# CAN_node_analog.net
KiCad netlist of a schematic drawn in EAGLE
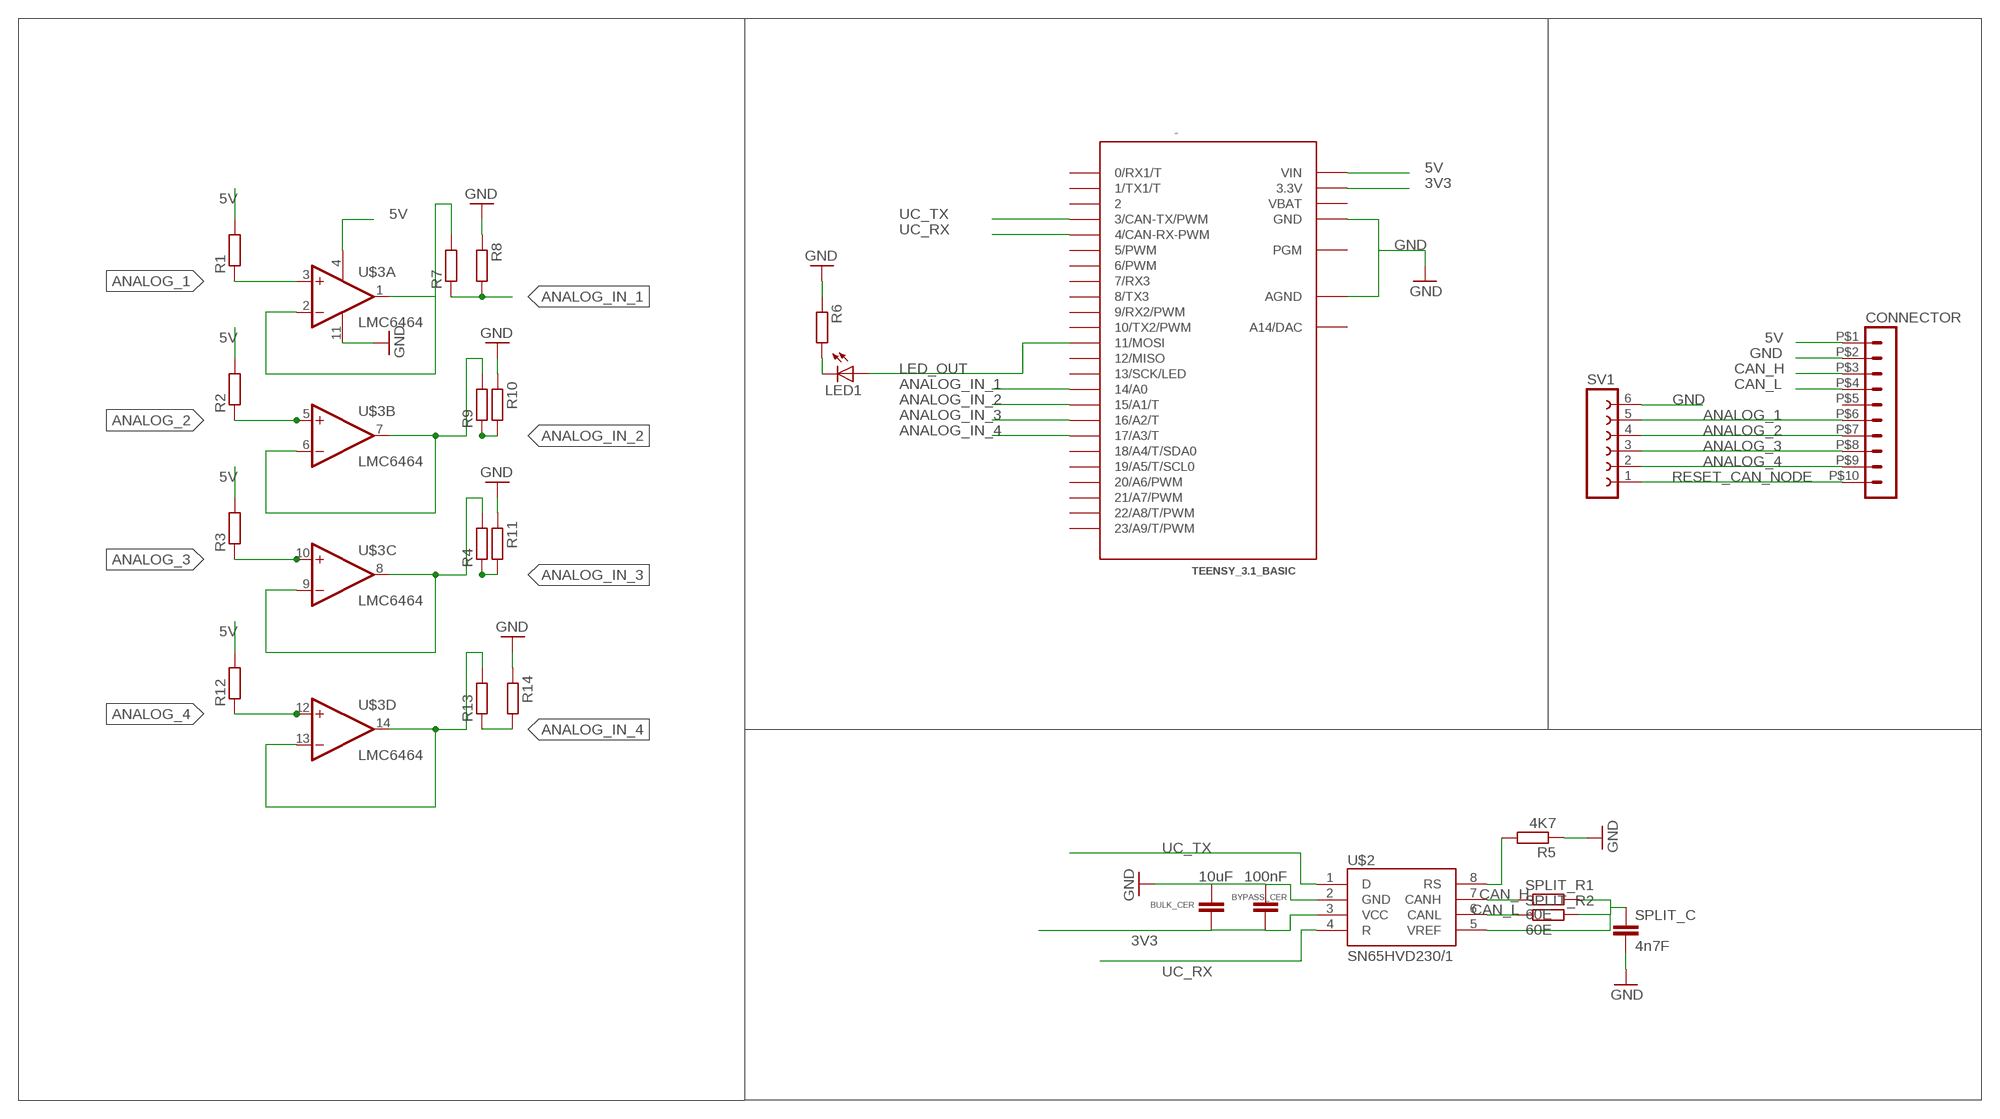
[diagram p0: schematic, sheet 1]

(export (version "E")
  (design (tool "Eeschema 10.0.6"))
  (components
    (comp (ref "BULK_CER")
      (value "10uF")
      (footprint "eagle-import:C0805")
      (libsource (lib "eagle-import") (part "C-EUC0805"))
    )
    (comp (ref "BYPASS_CER")
      (value "100nF")
      (footprint "eagle-import:C0805")
      (libsource (lib "eagle-import") (part "C-EUC0805"))
    )
    (comp (ref "CONNECTOR")
      (value "HEADER_POS10_43045-1012")
      (footprint "eagle-import:43045-1012")
      (libsource (lib "eagle-import") (part "HEADER_POS10_?43045-1012"))
    )
    (comp (ref "LED1")
      (value "LED1206")
      (footprint "eagle-import:LED-1206")
      (libsource (lib "eagle-import") (part "LED1206"))
    )
    (comp (ref "R1")
      (value "R-EU_R0805")
      (footprint "eagle-import:R0805")
      (libsource (lib "eagle-import") (part "R-EU_R0805"))
    )
    (comp (ref "R2")
      (value "R-EU_R0805")
      (footprint "eagle-import:R0805")
      (libsource (lib "eagle-import") (part "R-EU_R0805"))
    )
    (comp (ref "R3")
      (value "R-EU_R0805")
      (footprint "eagle-import:R0805")
      (libsource (lib "eagle-import") (part "R-EU_R0805"))
    )
    (comp (ref "R4")
      (value "R-EU_R0805")
      (footprint "eagle-import:R0805")
      (libsource (lib "eagle-import") (part "R-EU_R0805"))
    )
    (comp (ref "R5")
      (value "4K7")
      (footprint "eagle-import:R0805")
      (libsource (lib "eagle-import") (part "LV_R-EU_R0805"))
    )
    (comp (ref "R6")
      (value "R-EU_R0805")
      (footprint "eagle-import:R0805")
      (libsource (lib "eagle-import") (part "R-EU_R0805"))
    )
    (comp (ref "R7")
      (value "R-EU_R0805")
      (footprint "eagle-import:R0805")
      (libsource (lib "eagle-import") (part "R-EU_R0805"))
    )
    (comp (ref "R8")
      (value "R-EU_R0805")
      (footprint "eagle-import:R0805")
      (libsource (lib "eagle-import") (part "R-EU_R0805"))
    )
    (comp (ref "R9")
      (value "R-EU_R0805")
      (footprint "eagle-import:R0805")
      (libsource (lib "eagle-import") (part "R-EU_R0805"))
    )
    (comp (ref "R10")
      (value "R-EU_R0805")
      (footprint "eagle-import:R0805")
      (libsource (lib "eagle-import") (part "R-EU_R0805"))
    )
    (comp (ref "R11")
      (value "R-EU_R0805")
      (footprint "eagle-import:R0805")
      (libsource (lib "eagle-import") (part "R-EU_R0805"))
    )
    (comp (ref "R12")
      (value "R-EU_R0805")
      (footprint "eagle-import:R0805")
      (libsource (lib "eagle-import") (part "R-EU_R0805"))
    )
    (comp (ref "R13")
      (value "R-EU_R0805")
      (footprint "eagle-import:R0805")
      (libsource (lib "eagle-import") (part "R-EU_R0805"))
    )
    (comp (ref "R14")
      (value "R-EU_R0805")
      (footprint "eagle-import:R0805")
      (libsource (lib "eagle-import") (part "R-EU_R0805"))
    )
    (comp (ref "SPLIT_C")
      (value "4n7F")
      (footprint "eagle-import:C0805")
      (libsource (lib "eagle-import") (part "C-EUC0805"))
    )
    (comp (ref "SPLIT_R1")
      (value "60E")
      (footprint "eagle-import:R0805")
      (libsource (lib "eagle-import") (part "LV_R-EU_R0805"))
    )
    (comp (ref "SPLIT_R2")
      (value "60E")
      (footprint "eagle-import:R0805")
      (libsource (lib "eagle-import") (part "LV_R-EU_R0805"))
    )
    (comp (ref "SV1")
      (value "FE06-1")
      (footprint "eagle-import:FE06")
      (libsource (lib "eagle-import") (part "FE06-1"))
    )
    (comp (ref "U$1")
      (value "TEENSY_3.1_BASIC")
      (footprint "eagle-import:TEENSY_3.1_BASIC")
      (libsource (lib "eagle-import") (part "TEENSY_3.1_BASIC"))
    )
    (comp (ref "U$2")
      (value "SN65HVD230/1")
      (footprint "eagle-import:SO8")
      (libsource (lib "eagle-import") (part "SN65HVD230/1"))
    )
    (comp (ref "U$3")
      (value "LMC6464")
      (footprint "eagle-import:SO14_LONGPADS")
      (libsource (lib "eagle-import") (part "LMC6464"))
    )
  )
  (nets
    (net (code "1") (name "/3V3") (class "Default")
      (node (ref "BULK_CER") (pin "1") (pinfunction "1_1") (pintype "passive"))
      (node (ref "BYPASS_CER") (pin "1") (pinfunction "1_1") (pintype "passive"))
      (node (ref "U$1") (pin "3.3V") (pinfunction "3.3V_3.3V") (pintype "power_in"))
      (node (ref "U$1") (pin "3.3V1") (pinfunction "3.3V_3.3V1") (pintype "power_in"))
      (node (ref "U$2") (pin "3") (pinfunction "VCC_3") (pintype "power_in"))
    )
    (net (code "2") (name "/5V") (class "Default")
      (node (ref "CONNECTOR") (pin "P$1") (pinfunction "1_P$1") (pintype "passive"))
      (node (ref "R1") (pin "2") (pinfunction "2_2") (pintype "passive"))
      (node (ref "R12") (pin "2") (pinfunction "2_2") (pintype "passive"))
      (node (ref "R2") (pin "2") (pinfunction "2_2") (pintype "passive"))
      (node (ref "R3") (pin "2") (pinfunction "2_2") (pintype "passive"))
      (node (ref "U$1") (pin "VIN") (pinfunction "VIN_VIN") (pintype "power_in"))
      (node (ref "U$3") (pin "4") (pinfunction "V+_4") (pintype "power_in"))
    )
    (net (code "3") (name "/CAN_H") (class "Default")
      (node (ref "CONNECTOR") (pin "P$3") (pinfunction "3_P$3") (pintype "passive"))
      (node (ref "SPLIT_R1") (pin "1") (pinfunction "1_1") (pintype "passive"))
      (node (ref "U$2") (pin "7") (pinfunction "CANH_7") (pintype "bidirectional"))
    )
    (net (code "4") (name "/CAN_L") (class "Default")
      (node (ref "CONNECTOR") (pin "P$4") (pinfunction "4_P$4") (pintype "passive"))
      (node (ref "SPLIT_R2") (pin "1") (pinfunction "1_1") (pintype "passive"))
      (node (ref "U$2") (pin "6") (pinfunction "CANL_6") (pintype "bidirectional"))
    )
    (net (code "5") (name "/LED_OUT") (class "Default")
      (node (ref "LED1") (pin "A") (pinfunction "A_A") (pintype "passive"))
      (node (ref "U$1") (pin "11") (pinfunction "11/MOSI_11") (pintype "bidirectional"))
    )
    (net (code "6") (name "/RESET_CAN_NODE") (class "Default")
      (node (ref "CONNECTOR") (pin "P$10") (pinfunction "10_P$10") (pintype "passive"))
      (node (ref "SV1") (pin "1") (pinfunction "1_1") (pintype "passive"))
    )
    (net (code "7") (name "/UC_RX") (class "Default")
      (node (ref "U$1") (pin "4") (pinfunction "4/CAN-RX-PWM_4") (pintype "bidirectional"))
      (node (ref "U$2") (pin "4") (pinfunction "R_4") (pintype "bidirectional"))
    )
    (net (code "8") (name "/UC_TX") (class "Default")
      (node (ref "U$1") (pin "3") (pinfunction "3/CAN-TX/PWM_3") (pintype "bidirectional"))
      (node (ref "U$2") (pin "1") (pinfunction "D_1") (pintype "bidirectional"))
    )
    (net (code "9") (name "/VBAT") (class "Default")
      (node (ref "U$1") (pin "VBAT") (pinfunction "VBAT_VBAT") (pintype "power_in"))
    )
    (net (code "10") (name "ANALOG_1") (class "Default")
      (node (ref "CONNECTOR") (pin "P$6") (pinfunction "6_P$6") (pintype "passive"))
      (node (ref "R1") (pin "1") (pinfunction "1_1") (pintype "passive"))
      (node (ref "SV1") (pin "5") (pinfunction "5_5") (pintype "passive"))
      (node (ref "U$3") (pin "3") (pinfunction "+IN_3") (pintype "input"))
    )
    (net (code "11") (name "ANALOG_2") (class "Default")
      (node (ref "CONNECTOR") (pin "P$7") (pinfunction "7_P$7") (pintype "passive"))
      (node (ref "R2") (pin "1") (pinfunction "1_1") (pintype "passive"))
      (node (ref "SV1") (pin "4") (pinfunction "4_4") (pintype "passive"))
      (node (ref "U$3") (pin "5") (pinfunction "+IN_5") (pintype "input"))
    )
    (net (code "12") (name "ANALOG_3") (class "Default")
      (node (ref "CONNECTOR") (pin "P$8") (pinfunction "8_P$8") (pintype "passive"))
      (node (ref "R3") (pin "1") (pinfunction "1_1") (pintype "passive"))
      (node (ref "SV1") (pin "3") (pinfunction "3_3") (pintype "passive"))
      (node (ref "U$3") (pin "10") (pinfunction "+IN_10") (pintype "input"))
    )
    (net (code "13") (name "ANALOG_4") (class "Default")
      (node (ref "CONNECTOR") (pin "P$9") (pinfunction "9_P$9") (pintype "passive"))
      (node (ref "R12") (pin "1") (pinfunction "1_1") (pintype "passive"))
      (node (ref "SV1") (pin "2") (pinfunction "2_2") (pintype "passive"))
      (node (ref "U$3") (pin "12") (pinfunction "+IN_12") (pintype "input"))
    )
    (net (code "14") (name "ANALOG_IN_1") (class "Default")
      (node (ref "R7") (pin "1") (pinfunction "1_1") (pintype "passive"))
      (node (ref "R8") (pin "2") (pinfunction "2_2") (pintype "passive"))
      (node (ref "U$1") (pin "14/A0") (pinfunction "14/A0_14/A0") (pintype "bidirectional"))
    )
    (net (code "15") (name "ANALOG_IN_2") (class "Default")
      (node (ref "R10") (pin "2") (pinfunction "2_2") (pintype "passive"))
      (node (ref "R9") (pin "1") (pinfunction "1_1") (pintype "passive"))
      (node (ref "U$1") (pin "15/A1") (pinfunction "15/A1/T_15/A1") (pintype "bidirectional"))
    )
    (net (code "16") (name "ANALOG_IN_3") (class "Default")
      (node (ref "R11") (pin "2") (pinfunction "2_2") (pintype "passive"))
      (node (ref "R4") (pin "1") (pinfunction "1_1") (pintype "passive"))
      (node (ref "U$1") (pin "16/A2") (pinfunction "16/A2/T_16/A2") (pintype "bidirectional"))
    )
    (net (code "17") (name "ANALOG_IN_4") (class "Default")
      (node (ref "R13") (pin "1") (pinfunction "1_1") (pintype "passive"))
      (node (ref "R14") (pin "2") (pinfunction "2_2") (pintype "passive"))
      (node (ref "U$1") (pin "17/A3") (pinfunction "17/A3/T_17/A3") (pintype "bidirectional"))
    )
    (net (code "18") (name "GND") (class "Default")
      (node (ref "BULK_CER") (pin "2") (pinfunction "2_2") (pintype "passive"))
      (node (ref "BYPASS_CER") (pin "2") (pinfunction "2_2") (pintype "passive"))
      (node (ref "CONNECTOR") (pin "P$2") (pinfunction "2_P$2") (pintype "passive"))
      (node (ref "R10") (pin "1") (pinfunction "1_1") (pintype "passive"))
      (node (ref "R11") (pin "1") (pinfunction "1_1") (pintype "passive"))
      (node (ref "R14") (pin "1") (pinfunction "1_1") (pintype "passive"))
      (node (ref "R5") (pin "1") (pinfunction "1_1") (pintype "passive"))
      (node (ref "R6") (pin "1") (pinfunction "1_1") (pintype "passive"))
      (node (ref "R8") (pin "1") (pinfunction "1_1") (pintype "passive"))
      (node (ref "SPLIT_C") (pin "2") (pinfunction "2_2") (pintype "passive"))
      (node (ref "SV1") (pin "6") (pinfunction "6_6") (pintype "passive"))
      (node (ref "U$1") (pin "AGND") (pinfunction "AGND_AGND") (pintype "power_in"))
      (node (ref "U$1") (pin "GND") (pinfunction "GND_GND") (pintype "power_in"))
      (node (ref "U$1") (pin "GND1") (pinfunction "GND_GND1") (pintype "power_in"))
      (node (ref "U$2") (pin "2") (pinfunction "GND_2") (pintype "power_in"))
      (node (ref "U$3") (pin "11") (pinfunction "V-_11") (pintype "power_in"))
    )
    (net (code "19") (name "Net-(LED1-PadC)") (class "Default")
      (node (ref "LED1") (pin "C") (pinfunction "C_C") (pintype "passive"))
      (node (ref "R6") (pin "2") (pinfunction "2_2") (pintype "passive"))
    )
    (net (code "20") (name "Net-(U$2-RS)") (class "Default")
      (node (ref "R5") (pin "2") (pinfunction "2_2") (pintype "passive"))
      (node (ref "U$2") (pin "8") (pinfunction "RS_8") (pintype "bidirectional"))
    )
    (net (code "21") (name "Net-(U$2-VREF)") (class "Default")
      (node (ref "SPLIT_C") (pin "1") (pinfunction "1_1") (pintype "passive"))
      (node (ref "SPLIT_R1") (pin "2") (pinfunction "2_2") (pintype "passive"))
      (node (ref "SPLIT_R2") (pin "2") (pinfunction "2_2") (pintype "passive"))
      (node (ref "U$2") (pin "5") (pinfunction "VREF_5") (pintype "bidirectional"))
    )
    (net (code "22") (name "Net-(U$3A--IN)") (class "Default")
      (node (ref "R7") (pin "2") (pinfunction "2_2") (pintype "passive"))
      (node (ref "U$3") (pin "1") (pinfunction "OUT_1") (pintype "output"))
      (node (ref "U$3") (pin "2") (pinfunction "-IN_2") (pintype "input"))
    )
    (net (code "23") (name "Net-(U$3B--IN)") (class "Default")
      (node (ref "R9") (pin "2") (pinfunction "2_2") (pintype "passive"))
      (node (ref "U$3") (pin "6") (pinfunction "-IN_6") (pintype "input"))
      (node (ref "U$3") (pin "7") (pinfunction "OUT_7") (pintype "output"))
    )
    (net (code "24") (name "Net-(U$3C--IN)") (class "Default")
      (node (ref "R4") (pin "2") (pinfunction "2_2") (pintype "passive"))
      (node (ref "U$3") (pin "8") (pinfunction "OUT_8") (pintype "output"))
      (node (ref "U$3") (pin "9") (pinfunction "-IN_9") (pintype "input"))
    )
    (net (code "25") (name "Net-(U$3D--IN)") (class "Default")
      (node (ref "R13") (pin "2") (pinfunction "2_2") (pintype "passive"))
      (node (ref "U$3") (pin "13") (pinfunction "-IN_13") (pintype "input"))
      (node (ref "U$3") (pin "14") (pinfunction "OUT_14") (pintype "output"))
    )
    (net (code "26") (name "unconnected-(CONNECTOR-5-PadP$5)") (class "Default")
      (node (ref "CONNECTOR") (pin "P$5") (pinfunction "5_P$5") (pintype "passive"))
    )
    (net (code "27") (name "unconnected-(U$1-0{slash}RX1{slash}T-Pad0)") (class "Default")
      (node (ref "U$1") (pin "0") (pinfunction "0/RX1/T_0") (pintype "bidirectional"))
    )
    (net (code "28") (name "unconnected-(U$1-1{slash}TX1{slash}T-Pad1)") (class "Default")
      (node (ref "U$1") (pin "1") (pinfunction "1/TX1/T_1") (pintype "bidirectional"))
    )
    (net (code "29") (name "unconnected-(U$1-5{slash}PWM-Pad5)") (class "Default")
      (node (ref "U$1") (pin "5") (pinfunction "5/PWM_5") (pintype "bidirectional"))
    )
    (net (code "30") (name "unconnected-(U$1-6{slash}PWM-Pad6)") (class "Default")
      (node (ref "U$1") (pin "6") (pinfunction "6/PWM_6") (pintype "bidirectional"))
    )
    (net (code "31") (name "unconnected-(U$1-7{slash}RX3-Pad7)") (class "Default")
      (node (ref "U$1") (pin "7") (pinfunction "7/RX3_7") (pintype "bidirectional"))
    )
    (net (code "32") (name "unconnected-(U$1-8{slash}TX3-Pad8)") (class "Default")
      (node (ref "U$1") (pin "8") (pinfunction "8/TX3_8") (pintype "bidirectional"))
    )
    (net (code "33") (name "unconnected-(U$1-9{slash}RX2{slash}PWM-Pad9)") (class "Default")
      (node (ref "U$1") (pin "9") (pinfunction "9/RX2/PWM_9") (pintype "bidirectional"))
    )
    (net (code "34") (name "unconnected-(U$1-10{slash}TX2{slash}PWM-Pad10)") (class "Default")
      (node (ref "U$1") (pin "10") (pinfunction "10/TX2/PWM_10") (pintype "bidirectional"))
    )
    (net (code "35") (name "unconnected-(U$1-12{slash}MISO-Pad12)") (class "Default")
      (node (ref "U$1") (pin "12") (pinfunction "12/MISO_12") (pintype "bidirectional"))
    )
    (net (code "36") (name "unconnected-(U$1-13{slash}SCK{slash}LED-Pad13)") (class "Default")
      (node (ref "U$1") (pin "13") (pinfunction "13/SCK/LED_13") (pintype "bidirectional"))
    )
    (net (code "37") (name "unconnected-(U$1-18{slash}A4{slash}T{slash}SDA0-Pad18{slash}A4)") (class "Default")
      (node (ref "U$1") (pin "18/A4") (pinfunction "18/A4/T/SDA0_18/A4") (pintype "bidirectional"))
    )
    (net (code "38") (name "unconnected-(U$1-19{slash}A5{slash}T{slash}SCL0-Pad19{slash}A5)") (class "Default")
      (node (ref "U$1") (pin "19/A5") (pinfunction "19/A5/T/SCL0_19/A5") (pintype "bidirectional"))
    )
    (net (code "39") (name "unconnected-(U$1-20{slash}A6{slash}PWM-Pad20{slash}A6)") (class "Default")
      (node (ref "U$1") (pin "20/A6") (pinfunction "20/A6/PWM_20/A6") (pintype "bidirectional"))
    )
    (net (code "40") (name "unconnected-(U$1-21{slash}A7{slash}PWM-Pad21{slash}A7)") (class "Default")
      (node (ref "U$1") (pin "21/A7") (pinfunction "21/A7/PWM_21/A7") (pintype "bidirectional"))
    )
    (net (code "41") (name "unconnected-(U$1-22{slash}A8{slash}T{slash}PWM-Pad22{slash}A8)") (class "Default")
      (node (ref "U$1") (pin "22/A8") (pinfunction "22/A8/T/PWM_22/A8") (pintype "bidirectional"))
    )
    (net (code "42") (name "unconnected-(U$1-23{slash}A9{slash}T{slash}PWM-Pad23{slash}A9)") (class "Default")
      (node (ref "U$1") (pin "23/A9") (pinfunction "23/A9/T/PWM_23/A9") (pintype "bidirectional"))
    )
    (net (code "43") (name "unconnected-(U$1-A14{slash}DAC-PadA14)") (class "Default")
      (node (ref "U$1") (pin "A14") (pinfunction "A14/DAC_A14") (pintype "bidirectional"))
    )
    (net (code "44") (name "unconnected-(U$1-Pad2)") (class "Default")
      (node (ref "U$1") (pin "2") (pinfunction "2_2") (pintype "bidirectional"))
    )
    (net (code "45") (name "unconnected-(U$1-PadPGM)") (class "Default")
      (node (ref "U$1") (pin "PGM") (pinfunction "PGM_PGM") (pintype "bidirectional"))
    )
  )
)
